# Master_control_circuit.net
KiCad netlist of a schematic drawn in Altium Designer
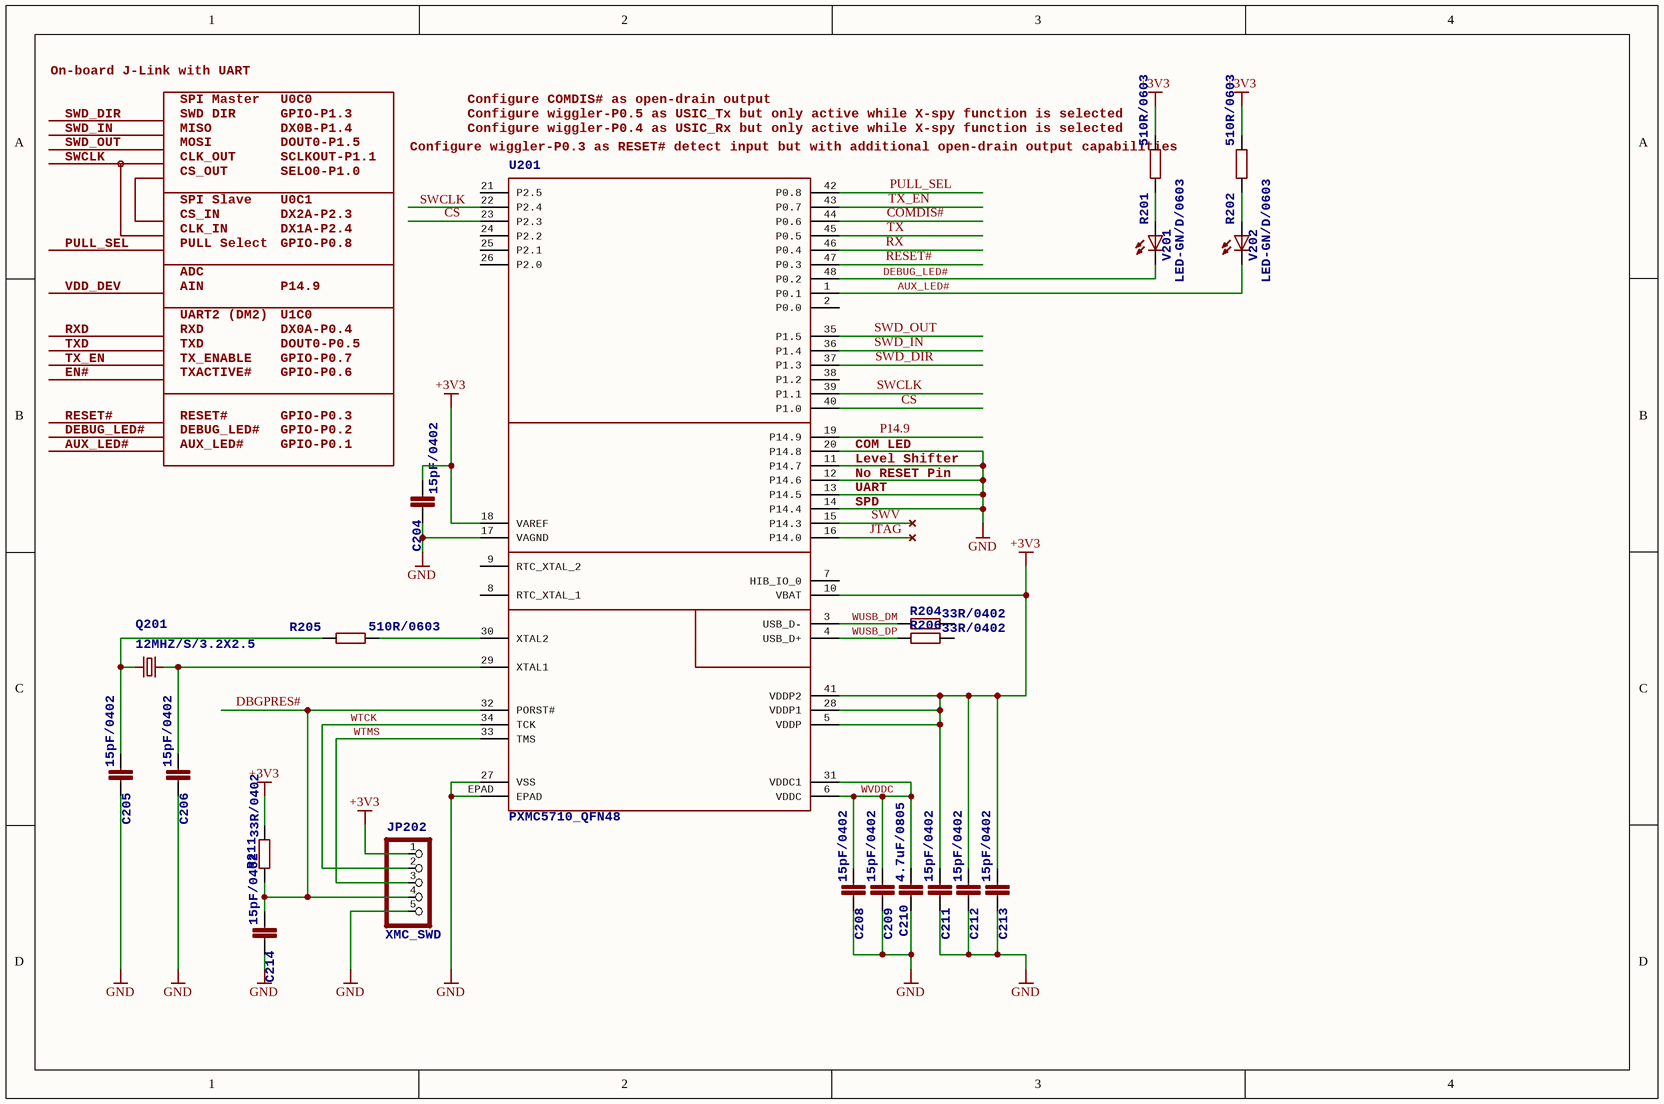
[diagram p0: Master control circuit.SchDoc]

(export (version "E")
  (design (tool "Eeschema 10.0.6"))
  (components
    (comp (ref "C204") (value "15pF/0402") (footprint "C0402") (libsource (lib "") (part "C-EUC0402_1")))
    (comp (ref "C205") (value "15pF/0402") (footprint "C0402") (libsource (lib "sucaiku") (part "C-EUC0402")))
    (comp (ref "C206") (value "15pF/0402") (footprint "C0402") (libsource (lib "sucaiku") (part "C-EUC0402")))
    (comp (ref "C208") (value "15pF/0402") (footprint "C0402") (libsource (lib "sucaiku") (part "C-EUC0402")))
    (comp (ref "C209") (value "15pF/0402") (footprint "C0402") (libsource (lib "sucaiku") (part "C-EUC0402")))
    (comp (ref "C210")
      (value "4.7uF/0805")
      (footprint "C0805K")
      (description "CAPACITOR, European symbol")
      (libsource (lib "sucaiku") (part "C-EUC0805K"))
    )
    (comp (ref "C211") (value "15pF/0402") (footprint "C0402") (libsource (lib "sucaiku") (part "C-EUC0402")))
    (comp (ref "C212") (value "15pF/0402") (footprint "C0402") (libsource (lib "sucaiku") (part "C-EUC0402")))
    (comp (ref "C213") (value "15pF/0402") (footprint "C0402") (libsource (lib "sucaiku") (part "C-EUC0402")))
    (comp (ref "C214") (value "15pF/0402") (footprint "C0402") (libsource (lib "sucaiku") (part "C-EUC0402")))
    (comp (ref "JP202")
      (value "XMC_SWD")
      (footprint "1X05")
      (description "PIN HEADER")
      (libsource (lib "sucaiku") (part "PINHD-1X5"))
    )
    (comp (ref "Q201")
      (value "12MHZ/S/3.2X2.5")
      (footprint "32X25_2PAD")
      (libsource (lib "sucaiku") (part "NX3225_22PAD"))
    )
    (comp (ref "R201")
      (value "510R/0603")
      (footprint "R0603")
      (libsource (lib "sucaiku") (part "R-EU_R0603"))
    )
    (comp (ref "R202")
      (value "510R/0603")
      (footprint "R0603")
      (libsource (lib "sucaiku") (part "R-EU_R0603"))
    )
    (comp (ref "R204") (value "33R/0402") (footprint "R0402") (libsource (lib "sucaiku") (part "R-EU_R0402")))
    (comp (ref "R205")
      (value "510R/0603")
      (footprint "R0603")
      (libsource (lib "sucaiku") (part "R-EU_R0603"))
    )
    (comp (ref "R206") (value "33R/0402") (footprint "R0402") (libsource (lib "sucaiku") (part "R-EU_R0402")))
    (comp (ref "R211") (value "33R/0402") (footprint "R0402") (libsource (lib "sucaiku") (part "R-EU_R0402")))
    (comp (ref "U201")
      (value "PXMC5710_QFN48")
      (footprint "QFN-48-7X7")
      (libsource (lib "sucaiku") (part "XMC4200_QFN48"))
    )
    (comp (ref "V201")
      (value "LED-GN/D/0603")
      (footprint "CHIPLED_0603")
      (libsource (lib "sucaiku") (part "LEDCHIPLED_0603"))
    )
    (comp (ref "V202")
      (value "LED-GN/D/0603")
      (footprint "CHIPLED_0603")
      (libsource (lib "sucaiku") (part "LEDCHIPLED_0603"))
    )
  )
  (nets
    (net (code "1") (name "+3V3") (class "Default")
      (node (ref "C204") (pin "1") (pinfunction "1_1") (pintype "passive"))
      (node (ref "C211") (pin "1") (pinfunction "1_1") (pintype "passive"))
      (node (ref "C212") (pin "1") (pinfunction "1_1") (pintype "passive"))
      (node (ref "C213") (pin "1") (pinfunction "1_1") (pintype "passive"))
      (node (ref "JP202") (pin "1") (pinfunction "1_1") (pintype "passive"))
      (node (ref "R201") (pin "1") (pinfunction "1_1") (pintype "passive"))
      (node (ref "R202") (pin "1") (pinfunction "1_1") (pintype "passive"))
      (node (ref "R211") (pin "2") (pinfunction "2_2") (pintype "passive"))
      (node (ref "U201") (pin "10") (pinfunction "VBAT_10") (pintype "passive"))
      (node (ref "U201") (pin "18") (pinfunction "VAREF_18") (pintype "passive"))
      (node (ref "U201") (pin "28") (pinfunction "VDDP1_28") (pintype "passive"))
      (node (ref "U201") (pin "41") (pinfunction "VDDP2_41") (pintype "passive"))
      (node (ref "U201") (pin "5") (pinfunction "VDDP_5") (pintype "passive"))
    )
    (net (code "2") (name "/AUX_LED#") (class "Default")
      (node (ref "U201") (pin "1") (pinfunction "P0.1_1") (pintype "passive"))
      (node (ref "V202") (pin "C") (pinfunction "C_C") (pintype "passive"))
    )
    (net (code "3") (name "/COMDIS#") (class "Default")
      (node (ref "U201") (pin "44") (pinfunction "P0.6_44") (pintype "passive"))
    )
    (net (code "4") (name "/CS") (class "Default")
      (node (ref "U201") (pin "23") (pinfunction "P2.3_23") (pintype "passive"))
      (node (ref "U201") (pin "40") (pinfunction "P1.0_40") (pintype "passive"))
    )
    (net (code "5") (name "/DBGPRES#") (class "Default")
      (node (ref "C214") (pin "1") (pinfunction "1_1") (pintype "passive"))
      (node (ref "JP202") (pin "4") (pinfunction "4_4") (pintype "passive"))
      (node (ref "R211") (pin "1") (pinfunction "1_1") (pintype "passive"))
      (node (ref "U201") (pin "32") (pinfunction "PORST#_32") (pintype "passive"))
    )
    (net (code "6") (name "/DEBUG_LED#") (class "Default")
      (node (ref "U201") (pin "48") (pinfunction "P0.2_48") (pintype "passive"))
      (node (ref "V201") (pin "C") (pinfunction "C_C") (pintype "passive"))
    )
    (net (code "7") (name "/JTAG") (class "Default")
      (node (ref "U201") (pin "16") (pinfunction "P14.0_16") (pintype "passive"))
    )
    (net (code "8") (name "/P14.9") (class "Default")
      (node (ref "U201") (pin "19") (pinfunction "P14.9_19") (pintype "passive"))
    )
    (net (code "9") (name "/PULL_SEL") (class "Default")
      (node (ref "U201") (pin "42") (pinfunction "P0.8_42") (pintype "passive"))
    )
    (net (code "10") (name "/RESET#") (class "Default")
      (node (ref "U201") (pin "47") (pinfunction "P0.3_47") (pintype "passive"))
    )
    (net (code "11") (name "/RX") (class "Default")
      (node (ref "U201") (pin "46") (pinfunction "P0.4_46") (pintype "passive"))
    )
    (net (code "12") (name "/SWCLK") (class "Default")
      (node (ref "U201") (pin "39") (pinfunction "P1.1_39") (pintype "passive"))
    )
    (net (code "13") (name "/SWD_DIR") (class "Default")
      (node (ref "U201") (pin "37") (pinfunction "P1.3_37") (pintype "passive"))
    )
    (net (code "14") (name "/SWD_IN") (class "Default")
      (node (ref "U201") (pin "36") (pinfunction "P1.4_36") (pintype "passive"))
    )
    (net (code "15") (name "/SWD_OUT") (class "Default")
      (node (ref "U201") (pin "35") (pinfunction "P1.5_35") (pintype "passive"))
    )
    (net (code "16") (name "/SWV") (class "Default")
      (node (ref "U201") (pin "15") (pinfunction "P14.3_15") (pintype "passive"))
    )
    (net (code "17") (name "/TX") (class "Default")
      (node (ref "U201") (pin "45") (pinfunction "P0.5_45") (pintype "passive"))
    )
    (net (code "18") (name "/TX_EN") (class "Default")
      (node (ref "U201") (pin "43") (pinfunction "P0.7_43") (pintype "passive"))
    )
    (net (code "19") (name "/WTCK") (class "Default")
      (node (ref "JP202") (pin "2") (pinfunction "2_2") (pintype "passive"))
      (node (ref "U201") (pin "34") (pinfunction "TCK_34") (pintype "passive"))
    )
    (net (code "20") (name "/WTMS") (class "Default")
      (node (ref "JP202") (pin "3") (pinfunction "3_3") (pintype "passive"))
      (node (ref "U201") (pin "33") (pinfunction "TMS_33") (pintype "passive"))
    )
    (net (code "21") (name "/WUSB_DM") (class "Default")
      (node (ref "R204") (pin "1") (pinfunction "1_1") (pintype "passive"))
      (node (ref "U201") (pin "3") (pinfunction "USB_D-_3") (pintype "passive"))
    )
    (net (code "22") (name "/WUSB_DP") (class "Default")
      (node (ref "R206") (pin "1") (pinfunction "1_1") (pintype "passive"))
      (node (ref "U201") (pin "4") (pinfunction "USB_D+_4") (pintype "passive"))
    )
    (net (code "23") (name "/WVDDC") (class "Default")
      (node (ref "C208") (pin "1") (pinfunction "1_1") (pintype "passive"))
      (node (ref "C209") (pin "1") (pinfunction "1_1") (pintype "passive"))
      (node (ref "C210") (pin "1") (pinfunction "1_1") (pintype "passive"))
      (node (ref "U201") (pin "31") (pinfunction "VDDC1_31") (pintype "passive"))
      (node (ref "U201") (pin "6") (pinfunction "VDDC_6") (pintype "passive"))
    )
    (net (code "24") (name "GND") (class "Default")
      (node (ref "C204") (pin "2") (pinfunction "2_2") (pintype "passive"))
      (node (ref "C205") (pin "2") (pinfunction "2_2") (pintype "passive"))
      (node (ref "C206") (pin "2") (pinfunction "2_2") (pintype "passive"))
      (node (ref "C208") (pin "2") (pinfunction "2_2") (pintype "passive"))
      (node (ref "C209") (pin "2") (pinfunction "2_2") (pintype "passive"))
      (node (ref "C210") (pin "2") (pinfunction "2_2") (pintype "passive"))
      (node (ref "C211") (pin "2") (pinfunction "2_2") (pintype "passive"))
      (node (ref "C212") (pin "2") (pinfunction "2_2") (pintype "passive"))
      (node (ref "C213") (pin "2") (pinfunction "2_2") (pintype "passive"))
      (node (ref "C214") (pin "2") (pinfunction "2_2") (pintype "passive"))
      (node (ref "JP202") (pin "5") (pinfunction "5_5") (pintype "passive"))
      (node (ref "U201") (pin "11") (pinfunction "P14.7_11") (pintype "passive"))
      (node (ref "U201") (pin "12") (pinfunction "P14.6_12") (pintype "passive"))
      (node (ref "U201") (pin "13") (pinfunction "P14.5_13") (pintype "passive"))
      (node (ref "U201") (pin "14") (pinfunction "P14.4_14") (pintype "passive"))
      (node (ref "U201") (pin "17") (pinfunction "VAGND_17") (pintype "passive"))
      (node (ref "U201") (pin "20") (pinfunction "P14.8_20") (pintype "passive"))
      (node (ref "U201") (pin "27") (pinfunction "VSS_27") (pintype "passive"))
      (node (ref "U201") (pin "EPAD") (pinfunction "EPAD_EPAD") (pintype "passive"))
    )
    (net (code "25") (name "Net-(C205-Pad1)") (class "Default")
      (node (ref "C205") (pin "1") (pinfunction "1_1") (pintype "passive"))
      (node (ref "Q201") (pin "2") (pinfunction "2_2") (pintype "passive"))
      (node (ref "R205") (pin "2") (pinfunction "2_2") (pintype "passive"))
    )
    (net (code "26") (name "Net-(R201-Pad2)") (class "Default")
      (node (ref "R201") (pin "2") (pinfunction "2_2") (pintype "passive"))
      (node (ref "V201") (pin "A") (pinfunction "A_A") (pintype "passive"))
    )
    (net (code "27") (name "Net-(R202-Pad2)") (class "Default")
      (node (ref "R202") (pin "2") (pinfunction "2_2") (pintype "passive"))
      (node (ref "V202") (pin "A") (pinfunction "A_A") (pintype "passive"))
    )
    (net (code "28") (name "Net-(U201-XTAL1)") (class "Default")
      (node (ref "C206") (pin "1") (pinfunction "1_1") (pintype "passive"))
      (node (ref "Q201") (pin "1") (pinfunction "1_1") (pintype "passive"))
      (node (ref "U201") (pin "29") (pinfunction "XTAL1_29") (pintype "passive"))
    )
    (net (code "29") (name "Net-(U201-XTAL2)") (class "Default")
      (node (ref "R205") (pin "1") (pinfunction "1_1") (pintype "passive"))
      (node (ref "U201") (pin "30") (pinfunction "XTAL2_30") (pintype "passive"))
    )
    (net (code "30") (name "unconnected-(R204-Pad2)") (class "Default")
      (node (ref "R204") (pin "2") (pinfunction "2_2") (pintype "passive"))
    )
    (net (code "31") (name "unconnected-(R206-Pad2)") (class "Default")
      (node (ref "R206") (pin "2") (pinfunction "2_2") (pintype "passive"))
    )
    (net (code "32") (name "unconnected-(U201-HIB_IO_0-Pad7)") (class "Default")
      (node (ref "U201") (pin "7") (pinfunction "HIB_IO_0_7") (pintype "passive"))
    )
    (net (code "33") (name "unconnected-(U201-P0.0-Pad2)") (class "Default")
      (node (ref "U201") (pin "2") (pinfunction "P0.0_2") (pintype "passive"))
    )
    (net (code "34") (name "unconnected-(U201-P1.2-Pad38)") (class "Default")
      (node (ref "U201") (pin "38") (pinfunction "P1.2_38") (pintype "passive"))
    )
    (net (code "35") (name "unconnected-(U201-P2.0-Pad26)") (class "Default")
      (node (ref "U201") (pin "26") (pinfunction "P2.0_26") (pintype "passive"))
    )
    (net (code "36") (name "unconnected-(U201-P2.1-Pad25)") (class "Default")
      (node (ref "U201") (pin "25") (pinfunction "P2.1_25") (pintype "passive"))
    )
    (net (code "37") (name "unconnected-(U201-P2.2-Pad24)") (class "Default")
      (node (ref "U201") (pin "24") (pinfunction "P2.2_24") (pintype "passive"))
    )
    (net (code "38") (name "unconnected-(U201-P2.4-Pad22)") (class "Default")
      (node (ref "U201") (pin "22") (pinfunction "P2.4_22") (pintype "passive"))
    )
    (net (code "39") (name "unconnected-(U201-P2.5-Pad21)") (class "Default")
      (node (ref "U201") (pin "21") (pinfunction "P2.5_21") (pintype "passive"))
    )
    (net (code "40") (name "unconnected-(U201-RTC_XTAL_1-Pad8)") (class "Default")
      (node (ref "U201") (pin "8") (pinfunction "RTC_XTAL_1_8") (pintype "passive"))
    )
    (net (code "41") (name "unconnected-(U201-RTC_XTAL_2-Pad9)") (class "Default")
      (node (ref "U201") (pin "9") (pinfunction "RTC_XTAL_2_9") (pintype "passive"))
    )
  )
)
